# STM32_Feather.net
KiCad netlist of a schematic drawn in EAGLE
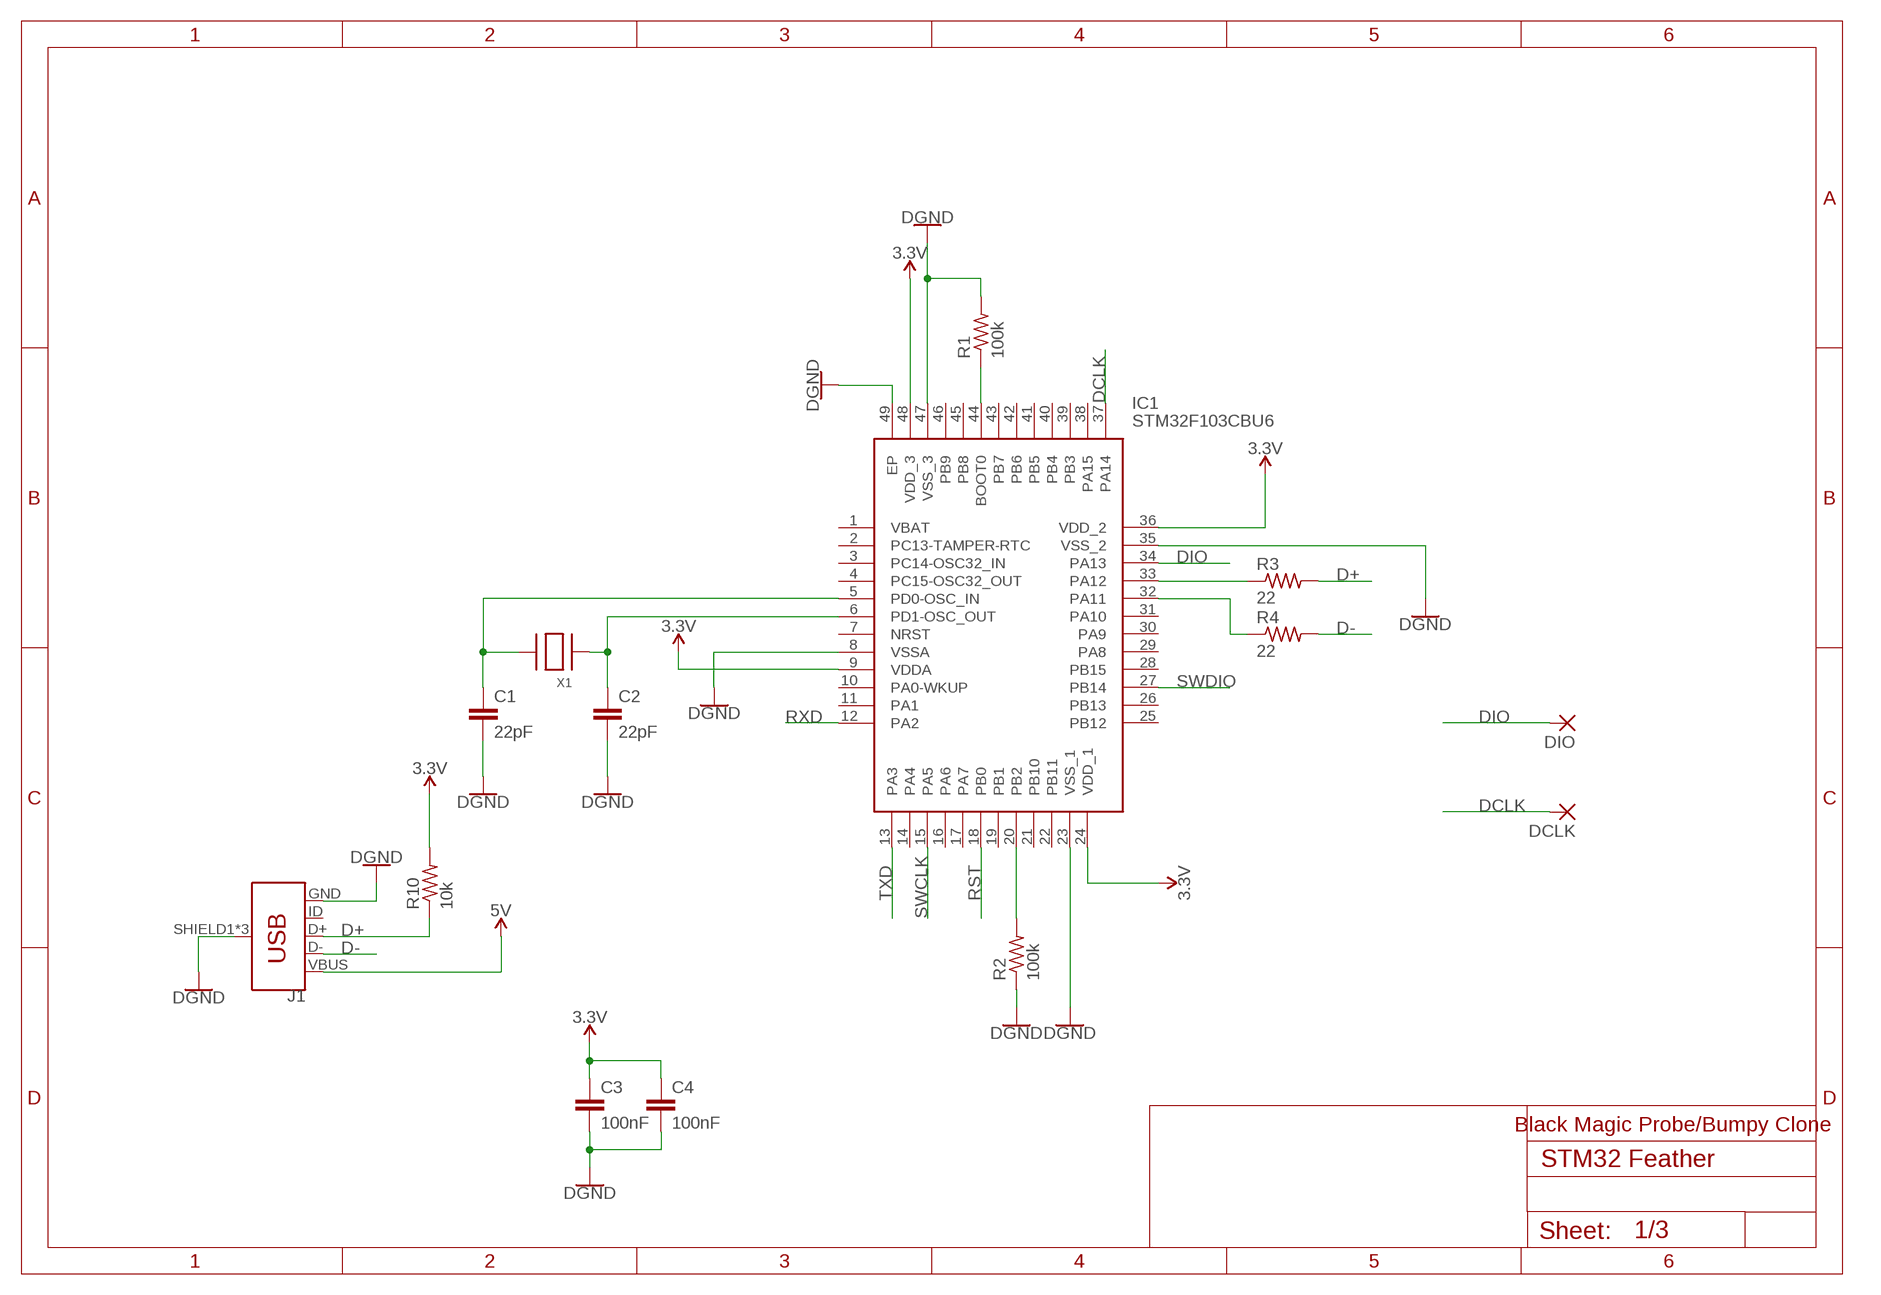
[diagram p0: schematic, sheet 1]
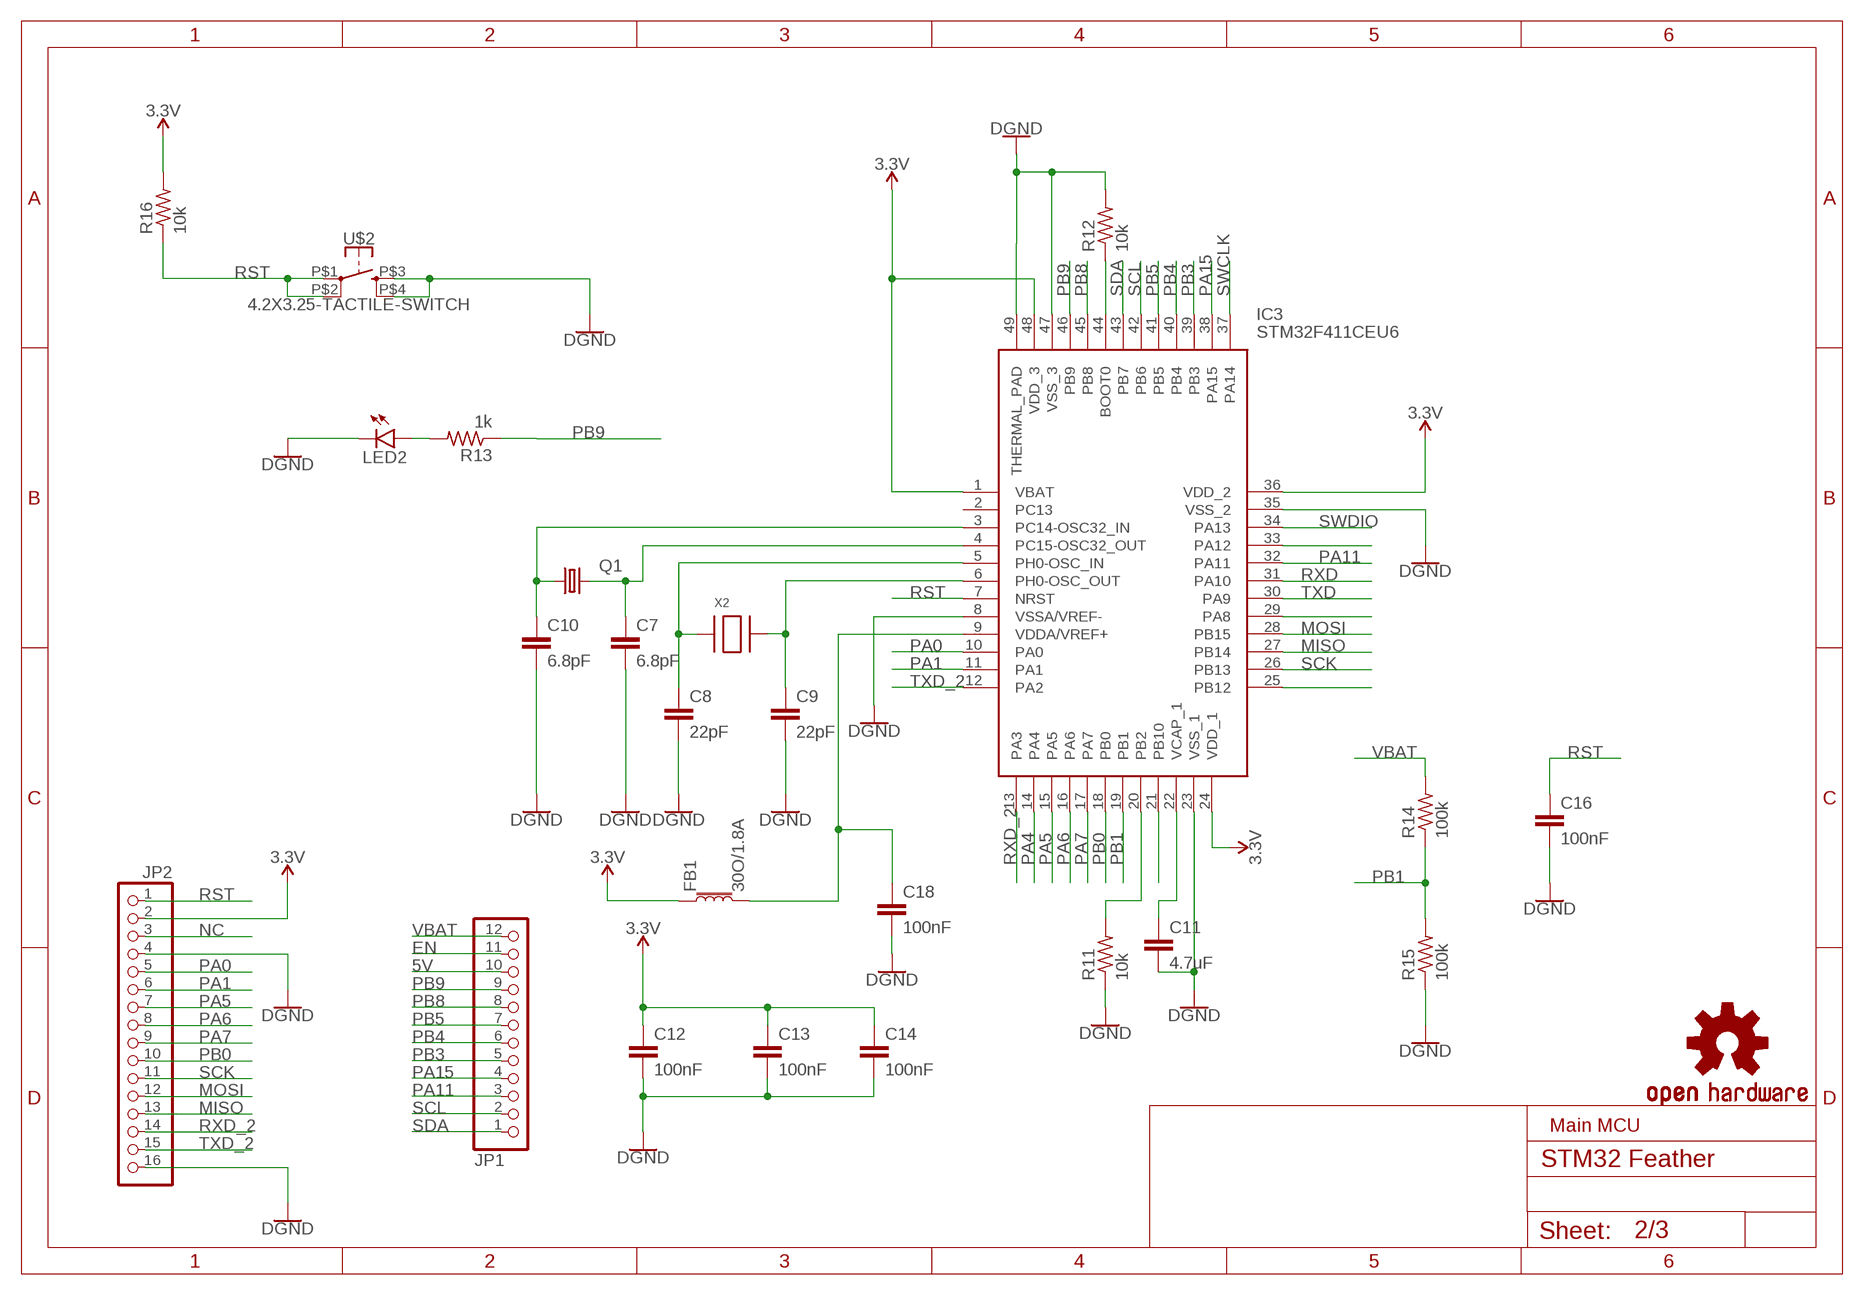
[diagram p1: schematic, sheet 2]
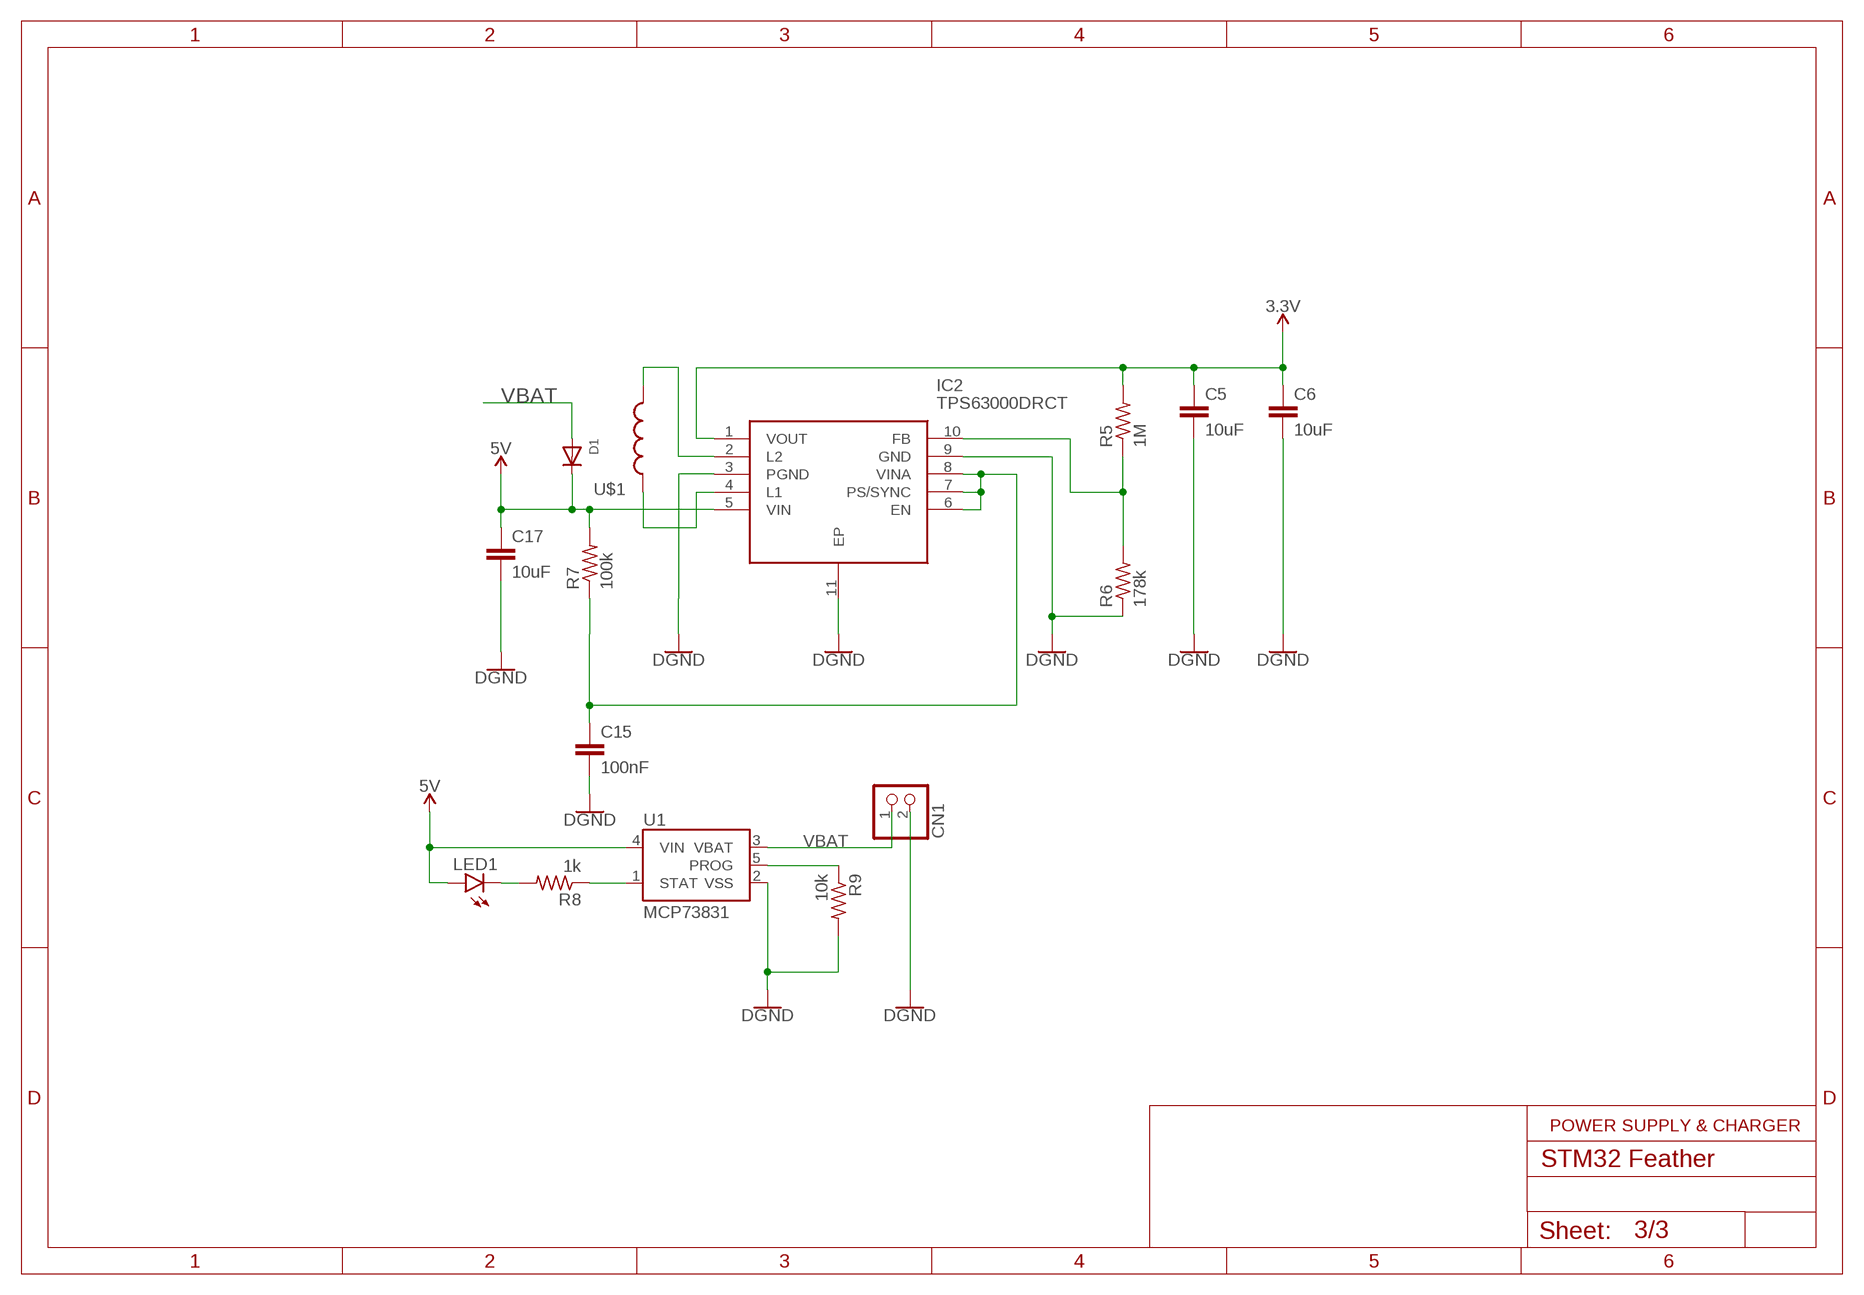
[diagram p2: schematic, sheet 3]

(export (version "E")
  (design (tool "Eeschema 10.0.6"))
  (components
    (comp (ref "C1")
      (value "22pF")
      (footprint "eagle-import:C0603")
      (libsource (lib "eagle-import") (part "C-EUC0603"))
    )
    (comp (ref "C2")
      (value "22pF")
      (footprint "eagle-import:C0603")
      (libsource (lib "eagle-import") (part "C-EUC0603"))
    )
    (comp (ref "C3")
      (value "100nF")
      (footprint "eagle-import:C0603")
      (libsource (lib "eagle-import") (part "C-EUC0603"))
    )
    (comp (ref "C4")
      (value "100nF")
      (footprint "eagle-import:C0603")
      (libsource (lib "eagle-import") (part "C-EUC0603"))
    )
    (comp (ref "DCLK")
      (value "SMD2")
      (footprint "eagle-import:SMD1,27-2,54")
      (libsource (lib "eagle-import") (part "SMD2"))
    )
    (comp (ref "DIO")
      (value "SMD2")
      (footprint "eagle-import:SMD1,27-2,54")
      (libsource (lib "eagle-import") (part "SMD2"))
    )
    (comp (ref "IC1")
      (value "STM32F103CBU6")
      (footprint "eagle-import:QFN50P700X700X65-49N")
      (fields
        (field (name "MOUSER_PART_NUMBER") "511-STM32F103CBU6")
        (field (name "RS_PART_NUMBER") "1687243")
      )
      (libsource (lib "eagle-import") (part "STM32F103CBU6"))
    )
    (comp (ref "J1")
      (value "USB_MICRO-B_FEMALE-SMT")
      (footprint "eagle-import:USB-B-MICRO-SMD")
      (libsource (lib "eagle-import") (part "USB_MICRO-B_FEMALE-SMT"))
    )
    (comp (ref "R1")
      (value "100k")
      (footprint "eagle-import:R0603")
      (libsource (lib "eagle-import") (part "R-US_R0603"))
    )
    (comp (ref "R2")
      (value "100k")
      (footprint "eagle-import:R0603")
      (libsource (lib "eagle-import") (part "R-US_R0603"))
    )
    (comp (ref "R3")
      (value "22")
      (footprint "eagle-import:R0603")
      (libsource (lib "eagle-import") (part "R-US_R0603"))
    )
    (comp (ref "R4")
      (value "22")
      (footprint "eagle-import:R0603")
      (libsource (lib "eagle-import") (part "R-US_R0603"))
    )
    (comp (ref "R10")
      (value "10k")
      (footprint "eagle-import:R0603")
      (libsource (lib "eagle-import") (part "R-US_R0603"))
    )
    (comp (ref "X1")
      (value "XTALNX5032")
      (footprint "eagle-import:NX5032")
      (libsource (lib "eagle-import") (part "XTALNX5032"))
    )
    (comp (ref "C5")
      (value "10uF")
      (footprint "eagle-import:C0805")
      (libsource (lib "eagle-import") (part "C-EUC0805"))
    )
    (comp (ref "C6")
      (value "10uF")
      (footprint "eagle-import:C0603")
      (libsource (lib "eagle-import") (part "C-EUC0603"))
    )
    (comp (ref "C15")
      (value "100nF")
      (footprint "eagle-import:C0603")
      (libsource (lib "eagle-import") (part "C-EUC0603"))
    )
    (comp (ref "C17")
      (value "10uF")
      (footprint "eagle-import:C0603")
      (libsource (lib "eagle-import") (part "C-EUC0603"))
    )
    (comp (ref "CN1")
      (value "JST_2PIN-THM-RA")
      (footprint "eagle-import:JST-PH-2-THM-RA")
      (libsource (lib "eagle-import") (part "JST_2PIN-THM-RA"))
    )
    (comp (ref "D1")
      (value "DIODESOD-123")
      (footprint "eagle-import:SOD-123")
      (libsource (lib "eagle-import") (part "DIODESOD-123"))
    )
    (comp (ref "IC2")
      (value "TPS63000DRCT")
      (footprint "eagle-import:SON50P300X300X100-11N")
      (fields
        (field (name "MOUSER_PART_NUMBER") "595-TPS63000DRCT")
        (field (name "RS_PART_NUMBER") "0389334P")
      )
      (libsource (lib "eagle-import") (part "TPS63000DRCT"))
    )
    (comp (ref "LED1")
      (value "LEDCHIPLED_0603")
      (footprint "eagle-import:CHIPLED_0603")
      (libsource (lib "eagle-import") (part "LEDCHIPLED_0603"))
    )
    (comp (ref "R5")
      (value "1M")
      (footprint "eagle-import:R0603")
      (libsource (lib "eagle-import") (part "R-US_R0603"))
    )
    (comp (ref "R6")
      (value "178k")
      (footprint "eagle-import:R0603")
      (libsource (lib "eagle-import") (part "R-US_R0603"))
    )
    (comp (ref "R7")
      (value "100k")
      (footprint "eagle-import:R0603")
      (libsource (lib "eagle-import") (part "R-US_R0603"))
    )
    (comp (ref "R8")
      (value "1k")
      (footprint "eagle-import:R0603")
      (libsource (lib "eagle-import") (part "R-US_R0603"))
    )
    (comp (ref "R9")
      (value "10k")
      (footprint "eagle-import:R0603")
      (libsource (lib "eagle-import") (part "R-US_R0603"))
    )
    (comp (ref "U$1")
      (value "SWPA252012S-INDUCTOR")
      (footprint "eagle-import:SWPA25012S")
      (libsource (lib "eagle-import") (part "SWPA252012S-INDUCTOR"))
    )
    (comp (ref "U1")
      (value "MCP73831")
      (footprint "eagle-import:SOT23-5")
      (libsource (lib "eagle-import") (part "MCP73831"))
    )
    (comp (ref "C7")
      (value "6.8pF")
      (footprint "eagle-import:C0603")
      (libsource (lib "eagle-import") (part "C-EUC0603"))
    )
    (comp (ref "C8")
      (value "22pF")
      (footprint "eagle-import:C0603")
      (libsource (lib "eagle-import") (part "C-EUC0603"))
    )
    (comp (ref "C9")
      (value "22pF")
      (footprint "eagle-import:C0603")
      (libsource (lib "eagle-import") (part "C-EUC0603"))
    )
    (comp (ref "C10")
      (value "6.8pF")
      (footprint "eagle-import:C0603")
      (libsource (lib "eagle-import") (part "C-EUC0603"))
    )
    (comp (ref "C11")
      (value "4.7uF")
      (footprint "eagle-import:C0603")
      (libsource (lib "eagle-import") (part "C-EUC0603"))
    )
    (comp (ref "C12")
      (value "100nF")
      (footprint "eagle-import:C0603")
      (libsource (lib "eagle-import") (part "C-EUC0603"))
    )
    (comp (ref "C13")
      (value "100nF")
      (footprint "eagle-import:C0603")
      (libsource (lib "eagle-import") (part "C-EUC0603"))
    )
    (comp (ref "C14")
      (value "100nF")
      (footprint "eagle-import:C0603")
      (libsource (lib "eagle-import") (part "C-EUC0603"))
    )
    (comp (ref "C16")
      (value "100nF")
      (footprint "eagle-import:C0603")
      (libsource (lib "eagle-import") (part "C-EUC0603"))
    )
    (comp (ref "C18")
      (value "100nF")
      (footprint "eagle-import:C0603")
      (libsource (lib "eagle-import") (part "C-EUC0603"))
    )
    (comp (ref "FB1")
      (value "30O/1.8A")
      (footprint "eagle-import:0603")
      (libsource (lib "eagle-import") (part "FERRITE_BEAD-0603"))
    )
    (comp (ref "IC3")
      (value "STM32F411CEU6")
      (footprint "eagle-import:QFN50P700X700X60-49N")
      (libsource (lib "eagle-import") (part "STM32F411CEU6"))
    )
    (comp (ref "JP1")
      (value "PINHD-1X12")
      (footprint "eagle-import:1X12")
      (libsource (lib "eagle-import") (part "PINHD-1X12"))
    )
    (comp (ref "JP2")
      (value "PINHD-1X16")
      (footprint "eagle-import:1X16")
      (libsource (lib "eagle-import") (part "PINHD-1X16"))
    )
    (comp (ref "LED2")
      (value "LEDCHIP-LED0603")
      (footprint "eagle-import:CHIP-LED0603")
      (libsource (lib "eagle-import") (part "LEDCHIP-LED0603"))
    )
    (comp (ref "LOGO1")
      (value "OSHW-LOGOMINI")
      (footprint "eagle-import:OSHW-LOGO-MINI")
      (libsource (lib "eagle-import") (part "OSHW-LOGOMINI"))
    )
    (comp (ref "Q1")
      (value "KX-327-NHF")
      (footprint "eagle-import:3.2X1.5")
      (libsource (lib "eagle-import") (part "KX-327-NHF"))
    )
    (comp (ref "R11")
      (value "10k")
      (footprint "eagle-import:R0603")
      (libsource (lib "eagle-import") (part "R-US_R0603"))
    )
    (comp (ref "R12")
      (value "10k")
      (footprint "eagle-import:R0603")
      (libsource (lib "eagle-import") (part "R-US_R0603"))
    )
    (comp (ref "R13")
      (value "1k")
      (footprint "eagle-import:R0603")
      (libsource (lib "eagle-import") (part "R-US_R0603"))
    )
    (comp (ref "R14")
      (value "100k")
      (footprint "eagle-import:R0603")
      (libsource (lib "eagle-import") (part "R-US_R0603"))
    )
    (comp (ref "R15")
      (value "100k")
      (footprint "eagle-import:R0603")
      (libsource (lib "eagle-import") (part "R-US_R0603"))
    )
    (comp (ref "R16")
      (value "10k")
      (footprint "eagle-import:R0603")
      (libsource (lib "eagle-import") (part "R-US_R0603"))
    )
    (comp (ref "U$2")
      (value "4.2X3.25-TACTILE-SWITCH")
      (footprint "eagle-import:4.2X3.25")
      (libsource (lib "eagle-import") (part "4.2X3.25-TACTILE-SWITCH"))
    )
    (comp (ref "X2")
      (value "XTALNX5032")
      (footprint "eagle-import:NX5032")
      (libsource (lib "eagle-import") (part "XTALNX5032"))
    )
  )
  (nets
    (net (code "1") (name "3.3V") (class "Default")
      (node (ref "C12") (pin "1") (pinfunction "1_1") (pintype "passive"))
      (node (ref "C13") (pin "1") (pinfunction "1_1") (pintype "passive"))
      (node (ref "C14") (pin "1") (pinfunction "1_1") (pintype "passive"))
      (node (ref "C3") (pin "1") (pinfunction "1_1") (pintype "passive"))
      (node (ref "C4") (pin "1") (pinfunction "1_1") (pintype "passive"))
      (node (ref "C5") (pin "1") (pinfunction "1_1") (pintype "passive"))
      (node (ref "C6") (pin "1") (pinfunction "1_1") (pintype "passive"))
      (node (ref "FB1") (pin "1") (pinfunction "1_1") (pintype "passive"))
      (node (ref "IC1") (pin "24") (pinfunction "VDD_1_24") (pintype "power_in"))
      (node (ref "IC1") (pin "36") (pinfunction "VDD_2_36") (pintype "power_in"))
      (node (ref "IC1") (pin "48") (pinfunction "VDD_3_48") (pintype "power_in"))
      (node (ref "IC1") (pin "9") (pinfunction "VDDA_9") (pintype "power_in"))
      (node (ref "IC2") (pin "1") (pinfunction "VOUT_1") (pintype "output"))
      (node (ref "IC3") (pin "1") (pinfunction "VBAT_1") (pintype "bidirectional"))
      (node (ref "IC3") (pin "24") (pinfunction "VDD_1_24") (pintype "bidirectional"))
      (node (ref "IC3") (pin "36") (pinfunction "VDD_2_36") (pintype "bidirectional"))
      (node (ref "IC3") (pin "48") (pinfunction "VDD_3_48") (pintype "bidirectional"))
      (node (ref "JP2") (pin "2") (pinfunction "2_2") (pintype "passive"))
      (node (ref "R10") (pin "2") (pinfunction "2_2") (pintype "passive"))
      (node (ref "R16") (pin "2") (pinfunction "2_2") (pintype "passive"))
      (node (ref "R5") (pin "2") (pinfunction "2_2") (pintype "passive"))
    )
    (net (code "2") (name "5V") (class "Default")
      (node (ref "C17") (pin "1") (pinfunction "1_1") (pintype "passive"))
      (node (ref "D1") (pin "C") (pinfunction "C_C") (pintype "passive"))
      (node (ref "IC2") (pin "5") (pinfunction "VIN_5") (pintype "input"))
      (node (ref "J1") (pin "VBUS") (pinfunction "VBUS_VBUS") (pintype "power_in"))
      (node (ref "JP1") (pin "10") (pinfunction "10_10") (pintype "passive"))
      (node (ref "LED1") (pin "A") (pinfunction "A_A") (pintype "passive"))
      (node (ref "R7") (pin "2") (pinfunction "2_2") (pintype "passive"))
      (node (ref "U1") (pin "4") (pinfunction "VIN_4") (pintype "power_in"))
    )
    (net (code "3") (name "D+") (class "Default")
      (node (ref "J1") (pin "D+") (pinfunction "D+_D+") (pintype "bidirectional"))
      (node (ref "R10") (pin "1") (pinfunction "1_1") (pintype "passive"))
      (node (ref "R3") (pin "2") (pinfunction "2_2") (pintype "passive"))
    )
    (net (code "4") (name "D-") (class "Default")
      (node (ref "J1") (pin "D-") (pinfunction "D-_D-") (pintype "bidirectional"))
      (node (ref "R4") (pin "2") (pinfunction "2_2") (pintype "passive"))
    )
    (net (code "5") (name "DCLK") (class "Default")
      (node (ref "DCLK") (pin "1") (pinfunction "P_1") (pintype "passive"))
      (node (ref "IC1") (pin "37") (pinfunction "PA14_37") (pintype "bidirectional"))
    )
    (net (code "6") (name "DIO") (class "Default")
      (node (ref "DIO") (pin "1") (pinfunction "P_1") (pintype "passive"))
      (node (ref "IC1") (pin "34") (pinfunction "PA13_34") (pintype "bidirectional"))
    )
    (net (code "7") (name "EN") (class "Default")
      (node (ref "JP1") (pin "11") (pinfunction "11_11") (pintype "passive"))
    )
    (net (code "8") (name "GND") (class "Default")
      (node (ref "C1") (pin "2") (pinfunction "2_2") (pintype "passive"))
      (node (ref "C10") (pin "2") (pinfunction "2_2") (pintype "passive"))
      (node (ref "C11") (pin "2") (pinfunction "2_2") (pintype "passive"))
      (node (ref "C12") (pin "2") (pinfunction "2_2") (pintype "passive"))
      (node (ref "C13") (pin "2") (pinfunction "2_2") (pintype "passive"))
      (node (ref "C14") (pin "2") (pinfunction "2_2") (pintype "passive"))
      (node (ref "C15") (pin "2") (pinfunction "2_2") (pintype "passive"))
      (node (ref "C16") (pin "2") (pinfunction "2_2") (pintype "passive"))
      (node (ref "C17") (pin "2") (pinfunction "2_2") (pintype "passive"))
      (node (ref "C18") (pin "2") (pinfunction "2_2") (pintype "passive"))
      (node (ref "C2") (pin "2") (pinfunction "2_2") (pintype "passive"))
      (node (ref "C3") (pin "2") (pinfunction "2_2") (pintype "passive"))
      (node (ref "C4") (pin "2") (pinfunction "2_2") (pintype "passive"))
      (node (ref "C5") (pin "2") (pinfunction "2_2") (pintype "passive"))
      (node (ref "C6") (pin "2") (pinfunction "2_2") (pintype "passive"))
      (node (ref "C7") (pin "2") (pinfunction "2_2") (pintype "passive"))
      (node (ref "C8") (pin "2") (pinfunction "2_2") (pintype "passive"))
      (node (ref "C9") (pin "2") (pinfunction "2_2") (pintype "passive"))
      (node (ref "CN1") (pin "2") (pinfunction "1_2") (pintype "passive"))
      (node (ref "IC1") (pin "23") (pinfunction "VSS_1_23") (pintype "power_in"))
      (node (ref "IC1") (pin "35") (pinfunction "VSS_2_35") (pintype "power_in"))
      (node (ref "IC1") (pin "47") (pinfunction "VSS_3_47") (pintype "power_in"))
      (node (ref "IC1") (pin "49") (pinfunction "EP_49") (pintype "bidirectional"))
      (node (ref "IC1") (pin "8") (pinfunction "VSSA_8") (pintype "power_in"))
      (node (ref "IC2") (pin "11") (pinfunction "EP_11") (pintype "bidirectional"))
      (node (ref "IC2") (pin "3") (pinfunction "PGND_3") (pintype "power_in"))
      (node (ref "IC2") (pin "9") (pinfunction "GND_9") (pintype "power_in"))
      (node (ref "IC3") (pin "23") (pinfunction "VSS_1_23") (pintype "bidirectional"))
      (node (ref "IC3") (pin "35") (pinfunction "VSS_2_35") (pintype "bidirectional"))
      (node (ref "IC3") (pin "47") (pinfunction "VSS_3_47") (pintype "bidirectional"))
      (node (ref "IC3") (pin "49") (pinfunction "THERMAL_PAD_49") (pintype "bidirectional"))
      (node (ref "IC3") (pin "8") (pinfunction "VSSA/VREF-_8") (pintype "bidirectional"))
      (node (ref "J1") (pin "GND") (pinfunction "GND_GND") (pintype "power_in"))
      (node (ref "J1") (pin "SHIELD1") (pinfunction "SHIELD_SHIELD1") (pintype "bidirectional"))
      (node (ref "J1") (pin "SHIELD2") (pinfunction "SHIELD_SHIELD2") (pintype "bidirectional"))
      (node (ref "J1") (pin "SHIELD3") (pinfunction "SHIELD_SHIELD3") (pintype "bidirectional"))
      (node (ref "JP2") (pin "16") (pinfunction "16_16") (pintype "passive"))
      (node (ref "JP2") (pin "4") (pinfunction "4_4") (pintype "passive"))
      (node (ref "LED2") (pin "C") (pinfunction "C_C") (pintype "passive"))
      (node (ref "R1") (pin "2") (pinfunction "2_2") (pintype "passive"))
      (node (ref "R11") (pin "1") (pinfunction "1_1") (pintype "passive"))
      (node (ref "R12") (pin "2") (pinfunction "2_2") (pintype "passive"))
      (node (ref "R15") (pin "1") (pinfunction "1_1") (pintype "passive"))
      (node (ref "R2") (pin "1") (pinfunction "1_1") (pintype "passive"))
      (node (ref "R6") (pin "1") (pinfunction "1_1") (pintype "passive"))
      (node (ref "R9") (pin "2") (pinfunction "2_2") (pintype "passive"))
      (node (ref "U$2") (pin "P$3") (pinfunction "3_P$3") (pintype "passive"))
      (node (ref "U$2") (pin "P$4") (pinfunction "4_P$4") (pintype "passive"))
      (node (ref "U1") (pin "2") (pinfunction "VSS_2") (pintype "power_in"))
    )
    (net (code "9") (name "MISO") (class "Default")
      (node (ref "IC3") (pin "27") (pinfunction "PB14_27") (pintype "bidirectional"))
      (node (ref "JP2") (pin "13") (pinfunction "13_13") (pintype "passive"))
    )
    (net (code "10") (name "MOSI") (class "Default")
      (node (ref "IC3") (pin "28") (pinfunction "PB15_28") (pintype "bidirectional"))
      (node (ref "JP2") (pin "12") (pinfunction "12_12") (pintype "passive"))
    )
    (net (code "11") (name "NC") (class "Default")
      (node (ref "JP2") (pin "3") (pinfunction "3_3") (pintype "passive"))
    )
    (net (code "12") (name "Net-(IC1-BOOT0)") (class "Default")
      (node (ref "IC1") (pin "44") (pinfunction "BOOT0_44") (pintype "bidirectional"))
      (node (ref "R1") (pin "1") (pinfunction "1_1") (pintype "passive"))
    )
    (net (code "13") (name "Net-(IC1-PA11)") (class "Default")
      (node (ref "IC1") (pin "32") (pinfunction "PA11_32") (pintype "bidirectional"))
      (node (ref "R4") (pin "1") (pinfunction "1_1") (pintype "passive"))
    )
    (net (code "14") (name "Net-(IC1-PA12)") (class "Default")
      (node (ref "IC1") (pin "33") (pinfunction "PA12_33") (pintype "bidirectional"))
      (node (ref "R3") (pin "1") (pinfunction "1_1") (pintype "passive"))
    )
    (net (code "15") (name "Net-(IC1-PB2)") (class "Default")
      (node (ref "IC1") (pin "20") (pinfunction "PB2_20") (pintype "bidirectional"))
      (node (ref "R2") (pin "2") (pinfunction "2_2") (pintype "passive"))
    )
    (net (code "16") (name "Net-(IC1-PD0-OSC_IN)") (class "Default")
      (node (ref "C1") (pin "1") (pinfunction "1_1") (pintype "passive"))
      (node (ref "IC1") (pin "5") (pinfunction "PD0-OSC_IN_5") (pintype "input"))
      (node (ref "X1") (pin "P$2") (pinfunction "P$2_P$2") (pintype "bidirectional"))
    )
    (net (code "17") (name "Net-(IC1-PD1-OSC_OUT)") (class "Default")
      (node (ref "C2") (pin "1") (pinfunction "1_1") (pintype "passive"))
      (node (ref "IC1") (pin "6") (pinfunction "PD1-OSC_OUT_6") (pintype "output"))
      (node (ref "X1") (pin "P$1") (pinfunction "P$1_P$1") (pintype "bidirectional"))
    )
    (net (code "18") (name "Net-(IC2-EN)") (class "Default")
      (node (ref "C15") (pin "1") (pinfunction "1_1") (pintype "passive"))
      (node (ref "IC2") (pin "6") (pinfunction "EN_6") (pintype "bidirectional"))
      (node (ref "IC2") (pin "7") (pinfunction "PS/SYNC_7") (pintype "bidirectional"))
      (node (ref "IC2") (pin "8") (pinfunction "VINA_8") (pintype "input"))
      (node (ref "R7") (pin "1") (pinfunction "1_1") (pintype "passive"))
    )
    (net (code "19") (name "Net-(IC2-FB)") (class "Default")
      (node (ref "IC2") (pin "10") (pinfunction "FB_10") (pintype "bidirectional"))
      (node (ref "R5") (pin "1") (pinfunction "1_1") (pintype "passive"))
      (node (ref "R6") (pin "2") (pinfunction "2_2") (pintype "passive"))
    )
    (net (code "20") (name "Net-(IC2-L1)") (class "Default")
      (node (ref "IC2") (pin "4") (pinfunction "L1_4") (pintype "bidirectional"))
      (node (ref "U$1") (pin "P$1") (pinfunction "1_P$1") (pintype "passive"))
    )
    (net (code "21") (name "Net-(IC2-L2)") (class "Default")
      (node (ref "IC2") (pin "2") (pinfunction "L2_2") (pintype "bidirectional"))
      (node (ref "U$1") (pin "P$2") (pinfunction "2_P$2") (pintype "passive"))
    )
    (net (code "22") (name "Net-(IC3-BOOT0)") (class "Default")
      (node (ref "IC3") (pin "44") (pinfunction "BOOT0_44") (pintype "bidirectional"))
      (node (ref "R12") (pin "1") (pinfunction "1_1") (pintype "passive"))
    )
    (net (code "23") (name "Net-(IC3-PB2)") (class "Default")
      (node (ref "IC3") (pin "20") (pinfunction "PB2_20") (pintype "bidirectional"))
      (node (ref "R11") (pin "2") (pinfunction "2_2") (pintype "passive"))
    )
    (net (code "24") (name "Net-(IC3-PC14-OSC32_IN)") (class "Default")
      (node (ref "C10") (pin "1") (pinfunction "1_1") (pintype "passive"))
      (node (ref "IC3") (pin "3") (pinfunction "PC14-OSC32_IN_3") (pintype "bidirectional"))
      (node (ref "Q1") (pin "1") (pinfunction "1_1") (pintype "passive"))
    )
    (net (code "25") (name "Net-(IC3-PC15-OSC32_OUT)") (class "Default")
      (node (ref "C7") (pin "1") (pinfunction "1_1") (pintype "passive"))
      (node (ref "IC3") (pin "4") (pinfunction "PC15-OSC32_OUT_4") (pintype "bidirectional"))
      (node (ref "Q1") (pin "2") (pinfunction "2_2") (pintype "passive"))
    )
    (net (code "26") (name "Net-(IC3-PH0-OSC_IN)") (class "Default")
      (node (ref "C8") (pin "1") (pinfunction "1_1") (pintype "passive"))
      (node (ref "IC3") (pin "5") (pinfunction "PH0-OSC_IN_5") (pintype "bidirectional"))
      (node (ref "X2") (pin "P$1") (pinfunction "P$1_P$1") (pintype "bidirectional"))
    )
    (net (code "27") (name "Net-(IC3-PH0-OSC_OUT)") (class "Default")
      (node (ref "C9") (pin "1") (pinfunction "1_1") (pintype "passive"))
      (node (ref "IC3") (pin "6") (pinfunction "PH0-OSC_OUT_6") (pintype "bidirectional"))
      (node (ref "X2") (pin "P$2") (pinfunction "P$2_P$2") (pintype "bidirectional"))
    )
    (net (code "28") (name "Net-(IC3-VCAP_1)") (class "Default")
      (node (ref "C11") (pin "1") (pinfunction "1_1") (pintype "passive"))
      (node (ref "IC3") (pin "22") (pinfunction "VCAP_1_22") (pintype "bidirectional"))
    )
    (net (code "29") (name "Net-(IC3-VDDA{slash}VREF+)") (class "Default")
      (node (ref "C18") (pin "1") (pinfunction "1_1") (pintype "passive"))
      (node (ref "FB1") (pin "2") (pinfunction "2_2") (pintype "passive"))
      (node (ref "IC3") (pin "9") (pinfunction "VDDA/VREF+_9") (pintype "bidirectional"))
    )
    (net (code "30") (name "Net-(LED1-PadC)") (class "Default")
      (node (ref "LED1") (pin "C") (pinfunction "C_C") (pintype "passive"))
      (node (ref "R8") (pin "2") (pinfunction "2_2") (pintype "passive"))
    )
    (net (code "31") (name "Net-(LED2-PadA)") (class "Default")
      (node (ref "LED2") (pin "A") (pinfunction "A_A") (pintype "passive"))
      (node (ref "R13") (pin "2") (pinfunction "2_2") (pintype "passive"))
    )
    (net (code "32") (name "Net-(U1-PROG)") (class "Default")
      (node (ref "R9") (pin "1") (pinfunction "1_1") (pintype "passive"))
      (node (ref "U1") (pin "5") (pinfunction "PROG_5") (pintype "input"))
    )
    (net (code "33") (name "Net-(U1-STAT)") (class "Default")
      (node (ref "R8") (pin "1") (pinfunction "1_1") (pintype "passive"))
      (node (ref "U1") (pin "1") (pinfunction "STAT_1") (pintype "output"))
    )
    (net (code "34") (name "PA0") (class "Default")
      (node (ref "IC3") (pin "10") (pinfunction "PA0_10") (pintype "bidirectional"))
      (node (ref "JP2") (pin "5") (pinfunction "5_5") (pintype "passive"))
    )
    (net (code "35") (name "PA1") (class "Default")
      (node (ref "IC3") (pin "11") (pinfunction "PA1_11") (pintype "bidirectional"))
      (node (ref "JP2") (pin "6") (pinfunction "6_6") (pintype "passive"))
    )
    (net (code "36") (name "PA4") (class "Default")
      (node (ref "IC3") (pin "14") (pinfunction "PA4_14") (pintype "bidirectional"))
    )
    (net (code "37") (name "PA5") (class "Default")
      (node (ref "IC3") (pin "15") (pinfunction "PA5_15") (pintype "bidirectional"))
      (node (ref "JP2") (pin "7") (pinfunction "7_7") (pintype "passive"))
    )
    (net (code "38") (name "PA6") (class "Default")
      (node (ref "IC3") (pin "16") (pinfunction "PA6_16") (pintype "bidirectional"))
      (node (ref "JP2") (pin "8") (pinfunction "8_8") (pintype "passive"))
    )
    (net (code "39") (name "PA7") (class "Default")
      (node (ref "IC3") (pin "17") (pinfunction "PA7_17") (pintype "bidirectional"))
      (node (ref "JP2") (pin "9") (pinfunction "9_9") (pintype "passive"))
    )
    (net (code "40") (name "PA11") (class "Default")
      (node (ref "IC3") (pin "32") (pinfunction "PA11_32") (pintype "bidirectional"))
      (node (ref "JP1") (pin "3") (pinfunction "3_3") (pintype "passive"))
    )
    (net (code "41") (name "PA15") (class "Default")
      (node (ref "IC3") (pin "38") (pinfunction "PA15_38") (pintype "bidirectional"))
      (node (ref "JP1") (pin "4") (pinfunction "4_4") (pintype "passive"))
    )
    (net (code "42") (name "PB0") (class "Default")
      (node (ref "IC3") (pin "18") (pinfunction "PB0_18") (pintype "bidirectional"))
      (node (ref "JP2") (pin "10") (pinfunction "10_10") (pintype "passive"))
    )
    (net (code "43") (name "PB1") (class "Default")
      (node (ref "IC3") (pin "19") (pinfunction "PB1_19") (pintype "bidirectional"))
      (node (ref "R14") (pin "1") (pinfunction "1_1") (pintype "passive"))
      (node (ref "R15") (pin "2") (pinfunction "2_2") (pintype "passive"))
    )
    (net (code "44") (name "PB3") (class "Default")
      (node (ref "IC3") (pin "39") (pinfunction "PB3_39") (pintype "bidirectional"))
      (node (ref "JP1") (pin "5") (pinfunction "5_5") (pintype "passive"))
    )
    (net (code "45") (name "PB4") (class "Default")
      (node (ref "IC3") (pin "40") (pinfunction "PB4_40") (pintype "bidirectional"))
      (node (ref "JP1") (pin "6") (pinfunction "6_6") (pintype "passive"))
    )
    (net (code "46") (name "PB5") (class "Default")
      (node (ref "IC3") (pin "41") (pinfunction "PB5_41") (pintype "bidirectional"))
      (node (ref "JP1") (pin "7") (pinfunction "7_7") (pintype "passive"))
    )
    (net (code "47") (name "PB8") (class "Default")
      (node (ref "IC3") (pin "45") (pinfunction "PB8_45") (pintype "bidirectional"))
      (node (ref "JP1") (pin "8") (pinfunction "8_8") (pintype "passive"))
    )
    (net (code "48") (name "PB9") (class "Default")
      (node (ref "IC3") (pin "46") (pinfunction "PB9_46") (pintype "bidirectional"))
      (node (ref "JP1") (pin "9") (pinfunction "9_9") (pintype "passive"))
      (node (ref "R13") (pin "1") (pinfunction "1_1") (pintype "passive"))
    )
    (net (code "49") (name "RST") (class "Default")
      (node (ref "C16") (pin "1") (pinfunction "1_1") (pintype "passive"))
      (node (ref "IC1") (pin "18") (pinfunction "PB0_18") (pintype "bidirectional"))
      (node (ref "IC3") (pin "7") (pinfunction "NRST_7") (pintype "bidirectional"))
      (node (ref "JP2") (pin "1") (pinfunction "1_1") (pintype "passive"))
      (node (ref "R16") (pin "1") (pinfunction "1_1") (pintype "passive"))
      (node (ref "U$2") (pin "P$1") (pinfunction "1_P$1") (pintype "passive"))
      (node (ref "U$2") (pin "P$2") (pinfunction "2_P$2") (pintype "passive"))
    )
    (net (code "50") (name "RXD") (class "Default")
      (node (ref "IC1") (pin "12") (pinfunction "PA2_12") (pintype "bidirectional"))
      (node (ref "IC3") (pin "31") (pinfunction "PA10_31") (pintype "bidirectional"))
    )
    (net (code "51") (name "RXD_2") (class "Default")
      (node (ref "IC3") (pin "13") (pinfunction "PA3_13") (pintype "bidirectional"))
      (node (ref "JP2") (pin "14") (pinfunction "14_14") (pintype "passive"))
    )
    (net (code "52") (name "SCK") (class "Default")
      (node (ref "IC3") (pin "26") (pinfunction "PB13_26") (pintype "bidirectional"))
      (node (ref "JP2") (pin "11") (pinfunction "11_11") (pintype "passive"))
    )
    (net (code "53") (name "SCL") (class "Default")
      (node (ref "IC3") (pin "42") (pinfunction "PB6_42") (pintype "bidirectional"))
      (node (ref "JP1") (pin "2") (pinfunction "2_2") (pintype "passive"))
    )
    (net (code "54") (name "SDA") (class "Default")
      (node (ref "IC3") (pin "43") (pinfunction "PB7_43") (pintype "bidirectional"))
      (node (ref "JP1") (pin "1") (pinfunction "1_1") (pintype "passive"))
    )
    (net (code "55") (name "SWCLK") (class "Default")
      (node (ref "IC1") (pin "15") (pinfunction "PA5_15") (pintype "bidirectional"))
      (node (ref "IC3") (pin "37") (pinfunction "PA14_37") (pintype "bidirectional"))
    )
    (net (code "56") (name "SWDIO") (class "Default")
      (node (ref "IC1") (pin "27") (pinfunction "PB14_27") (pintype "bidirectional"))
      (node (ref "IC3") (pin "34") (pinfunction "PA13_34") (pintype "bidirectional"))
    )
    (net (code "57") (name "TXD") (class "Default")
      (node (ref "IC1") (pin "13") (pinfunction "PA3_13") (pintype "bidirectional"))
      (node (ref "IC3") (pin "30") (pinfunction "PA9_30") (pintype "bidirectional"))
    )
    (net (code "58") (name "TXD_2") (class "Default")
      (node (ref "IC3") (pin "12") (pinfunction "PA2_12") (pintype "bidirectional"))
      (node (ref "JP2") (pin "15") (pinfunction "15_15") (pintype "passive"))
    )
    (net (code "59") (name "VBAT") (class "Default")
      (node (ref "CN1") (pin "1") (pinfunction "2_1") (pintype "passive"))
      (node (ref "D1") (pin "A") (pinfunction "A_A") (pintype "passive"))
      (node (ref "JP1") (pin "12") (pinfunction "12_12") (pintype "passive"))
      (node (ref "R14") (pin "2") (pinfunction "2_2") (pintype "passive"))
      (node (ref "U1") (pin "3") (pinfunction "VBAT_3") (pintype "power_in"))
    )
    (net (code "60") (name "unconnected-(IC1-NRST-Pad7)") (class "Default")
      (node (ref "IC1") (pin "7") (pinfunction "NRST_7") (pintype "input"))
    )
    (net (code "61") (name "unconnected-(IC1-PA0-WKUP-Pad10)") (class "Default")
      (node (ref "IC1") (pin "10") (pinfunction "PA0-WKUP_10") (pintype "bidirectional"))
    )
    (net (code "62") (name "unconnected-(IC1-PA1-Pad11)") (class "Default")
      (node (ref "IC1") (pin "11") (pinfunction "PA1_11") (pintype "bidirectional"))
    )
    (net (code "63") (name "unconnected-(IC1-PA4-Pad14)") (class "Default")
      (node (ref "IC1") (pin "14") (pinfunction "PA4_14") (pintype "bidirectional"))
    )
    (net (code "64") (name "unconnected-(IC1-PA6-Pad16)") (class "Default")
      (node (ref "IC1") (pin "16") (pinfunction "PA6_16") (pintype "bidirectional"))
    )
    (net (code "65") (name "unconnected-(IC1-PA7-Pad17)") (class "Default")
      (node (ref "IC1") (pin "17") (pinfunction "PA7_17") (pintype "bidirectional"))
    )
    (net (code "66") (name "unconnected-(IC1-PA8-Pad29)") (class "Default")
      (node (ref "IC1") (pin "29") (pinfunction "PA8_29") (pintype "bidirectional"))
    )
    (net (code "67") (name "unconnected-(IC1-PA9-Pad30)") (class "Default")
      (node (ref "IC1") (pin "30") (pinfunction "PA9_30") (pintype "bidirectional"))
    )
    (net (code "68") (name "unconnected-(IC1-PA10-Pad31)") (class "Default")
      (node (ref "IC1") (pin "31") (pinfunction "PA10_31") (pintype "bidirectional"))
    )
    (net (code "69") (name "unconnected-(IC1-PA15-Pad38)") (class "Default")
      (node (ref "IC1") (pin "38") (pinfunction "PA15_38") (pintype "bidirectional"))
    )
    (net (code "70") (name "unconnected-(IC1-PB1-Pad19)") (class "Default")
      (node (ref "IC1") (pin "19") (pinfunction "PB1_19") (pintype "bidirectional"))
    )
    (net (code "71") (name "unconnected-(IC1-PB3-Pad39)") (class "Default")
      (node (ref "IC1") (pin "39") (pinfunction "PB3_39") (pintype "bidirectional"))
    )
    (net (code "72") (name "unconnected-(IC1-PB4-Pad40)") (class "Default")
      (node (ref "IC1") (pin "40") (pinfunction "PB4_40") (pintype "bidirectional"))
    )
    (net (code "73") (name "unconnected-(IC1-PB5-Pad41)") (class "Default")
      (node (ref "IC1") (pin "41") (pinfunction "PB5_41") (pintype "bidirectional"))
    )
    (net (code "74") (name "unconnected-(IC1-PB6-Pad42)") (class "Default")
      (node (ref "IC1") (pin "42") (pinfunction "PB6_42") (pintype "bidirectional"))
    )
    (net (code "75") (name "unconnected-(IC1-PB7-Pad43)") (class "Default")
      (node (ref "IC1") (pin "43") (pinfunction "PB7_43") (pintype "bidirectional"))
    )
    (net (code "76") (name "unconnected-(IC1-PB8-Pad45)") (class "Default")
      (node (ref "IC1") (pin "45") (pinfunction "PB8_45") (pintype "bidirectional"))
    )
    (net (code "77") (name "unconnected-(IC1-PB9-Pad46)") (class "Default")
      (node (ref "IC1") (pin "46") (pinfunction "PB9_46") (pintype "bidirectional"))
    )
    (net (code "78") (name "unconnected-(IC1-PB10-Pad21)") (class "Default")
      (node (ref "IC1") (pin "21") (pinfunction "PB10_21") (pintype "bidirectional"))
    )
    (net (code "79") (name "unconnected-(IC1-PB11-Pad22)") (class "Default")
      (node (ref "IC1") (pin "22") (pinfunction "PB11_22") (pintype "bidirectional"))
    )
    (net (code "80") (name "unconnected-(IC1-PB12-Pad25)") (class "Default")
      (node (ref "IC1") (pin "25") (pinfunction "PB12_25") (pintype "bidirectional"))
    )
    (net (code "81") (name "unconnected-(IC1-PB13-Pad26)") (class "Default")
      (node (ref "IC1") (pin "26") (pinfunction "PB13_26") (pintype "bidirectional"))
    )
    (net (code "82") (name "unconnected-(IC1-PB15-Pad28)") (class "Default")
      (node (ref "IC1") (pin "28") (pinfunction "PB15_28") (pintype "bidirectional"))
    )
    (net (code "83") (name "unconnected-(IC1-PC13-TAMPER-RTC-Pad2)") (class "Default")
      (node (ref "IC1") (pin "2") (pinfunction "PC13-TAMPER-RTC_2") (pintype "bidirectional"))
    )
    (net (code "84") (name "unconnected-(IC1-PC14-OSC32_IN-Pad3)") (class "Default")
      (node (ref "IC1") (pin "3") (pinfunction "PC14-OSC32_IN_3") (pintype "input"))
    )
    (net (code "85") (name "unconnected-(IC1-PC15-OSC32_OUT-Pad4)") (class "Default")
      (node (ref "IC1") (pin "4") (pinfunction "PC15-OSC32_OUT_4") (pintype "output"))
    )
    (net (code "86") (name "unconnected-(IC1-VBAT-Pad1)") (class "Default")
      (node (ref "IC1") (pin "1") (pinfunction "VBAT_1") (pintype "bidirectional"))
    )
    (net (code "87") (name "unconnected-(IC3-PA8-Pad29)") (class "Default")
      (node (ref "IC3") (pin "29") (pinfunction "PA8_29") (pintype "bidirectional"))
    )
    (net (code "88") (name "unconnected-(IC3-PA12-Pad33)") (class "Default")
      (node (ref "IC3") (pin "33") (pinfunction "PA12_33") (pintype "bidirectional"))
    )
    (net (code "89") (name "unconnected-(IC3-PB10-Pad21)") (class "Default")
      (node (ref "IC3") (pin "21") (pinfunction "PB10_21") (pintype "bidirectional"))
    )
    (net (code "90") (name "unconnected-(IC3-PB12-Pad25)") (class "Default")
      (node (ref "IC3") (pin "25") (pinfunction "PB12_25") (pintype "bidirectional"))
    )
    (net (code "91") (name "unconnected-(IC3-PC13-Pad2)") (class "Default")
      (node (ref "IC3") (pin "2") (pinfunction "PC13_2") (pintype "bidirectional"))
    )
    (net (code "92") (name "unconnected-(J1-PadID)") (class "Default")
      (node (ref "J1") (pin "ID") (pinfunction "ID_ID") (pintype "bidirectional"))
    )
  )
)
